# Sincronismo.net
KiCad netlist of a schematic drawn in Altium Designer
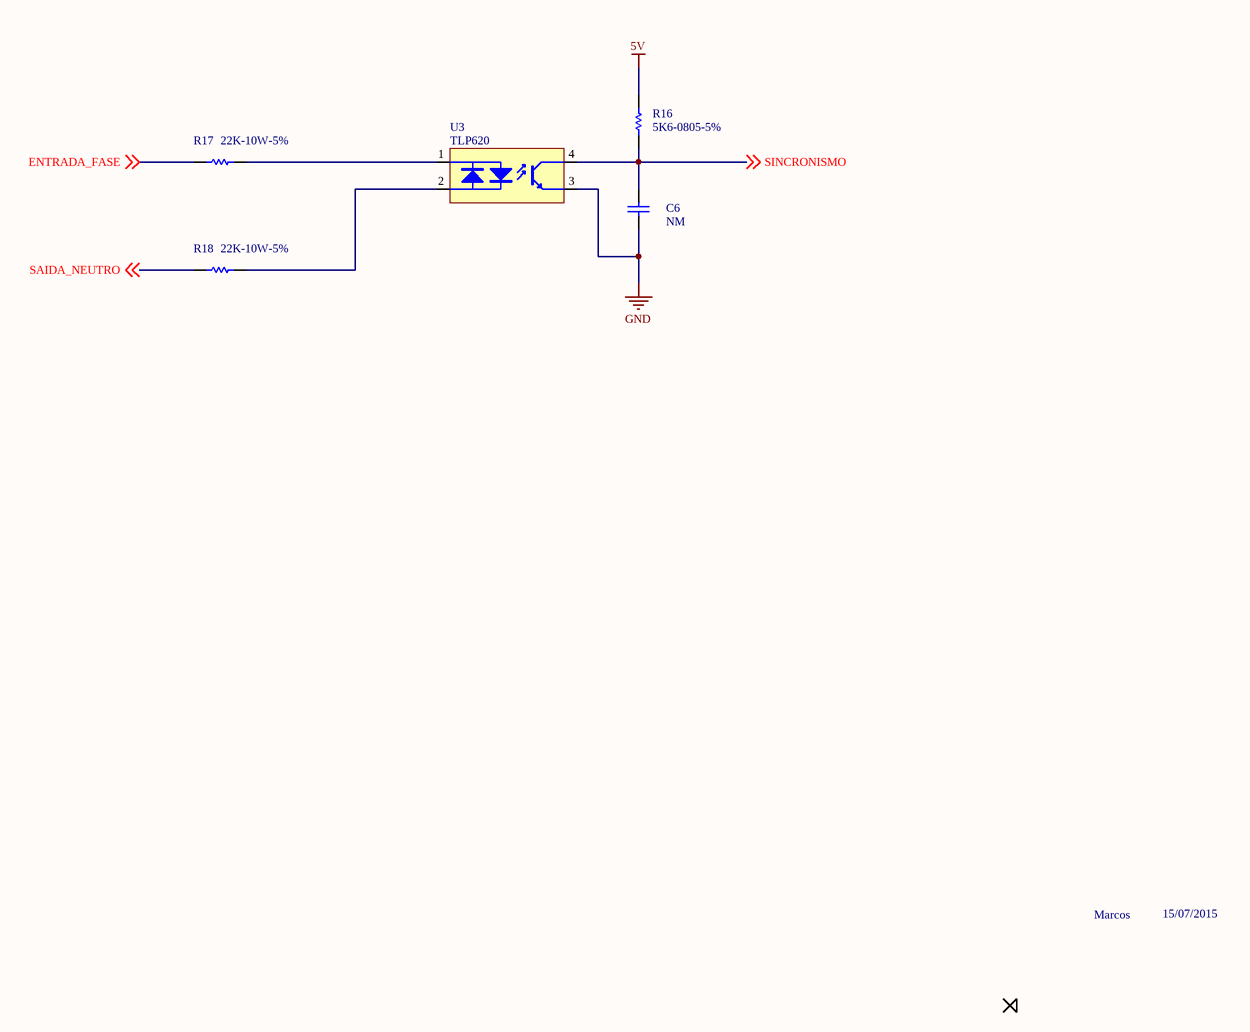
[diagram p0: Sincronismo.SchDoc]

(export (version "E")
  (design (tool "Eeschema 10.0.6"))
  (components
    (comp (ref "C6")
      (value "NM")
      (footprint "0805-REVISADO ONDA")
      (description "100nF/50-0805-NPO")
      (libsource (lib "AquinoLib") (part "100nF/50-0805-NPO"))
    )
    (comp (ref "R16")
      (value "5K6-0805-5%")
      (footprint "0805-REVISADO ONDA")
      (description "22K-0805-5%")
      (libsource (lib "AquinoLib") (part "22K-0805-5%"))
    )
    (comp (ref "R17")
      (value "22K-10W-5%")
      (footprint "RESISTOR 10W CERAMICO")
      (description "22K-0805-5%")
      (libsource (lib "AquinoLib") (part "22K-0805-5%"))
    )
    (comp (ref "R18")
      (value "22K-10W-5%")
      (footprint "RESISTOR 10W CERAMICO")
      (description "22K-0805-5%")
      (libsource (lib "AquinoLib") (part "22K-0805-5%"))
    )
    (comp (ref "U3")
      (value "TLP620")
      (footprint "DIP-4")
      (description "PC814")
      (libsource (lib "AquinoLib") (part "PC814"))
    )
  )
  (nets
    (net (code "1") (name "5V") (class "Default")
      (node (ref "R16") (pin "2") (pinfunction "2_2") (pintype "passive"))
    )
    (net (code "2") (name "ENTRADA_FASE") (class "Default")
      (node (ref "R17") (pin "1") (pinfunction "1_1") (pintype "passive"))
    )
    (net (code "3") (name "GND") (class "Default")
      (node (ref "C6") (pin "1") (pinfunction "1_1") (pintype "passive"))
      (node (ref "U3") (pin "3") (pinfunction "E_3") (pintype "passive"))
    )
    (net (code "4") (name "Net-(U3-A)") (class "Default")
      (node (ref "R17") (pin "2") (pinfunction "2_2") (pintype "passive"))
      (node (ref "U3") (pin "1") (pinfunction "A_1") (pintype "passive"))
    )
    (net (code "5") (name "Net-(U3-K)") (class "Default")
      (node (ref "R18") (pin "2") (pinfunction "2_2") (pintype "passive"))
      (node (ref "U3") (pin "2") (pinfunction "K_2") (pintype "passive"))
    )
    (net (code "6") (name "SAIDA_NEUTRO") (class "Default")
      (node (ref "R18") (pin "1") (pinfunction "1_1") (pintype "passive"))
    )
    (net (code "7") (name "SINCRONISMO") (class "Default")
      (node (ref "C6") (pin "2") (pinfunction "2_2") (pintype "passive"))
      (node (ref "R16") (pin "1") (pinfunction "1_1") (pintype "passive"))
      (node (ref "U3") (pin "4") (pinfunction "C_4") (pintype "passive"))
    )
  )
)
